# CSI2-TX2-XAVIER_Rev02.net
KiCad netlist of a schematic drawn in Altium Designer
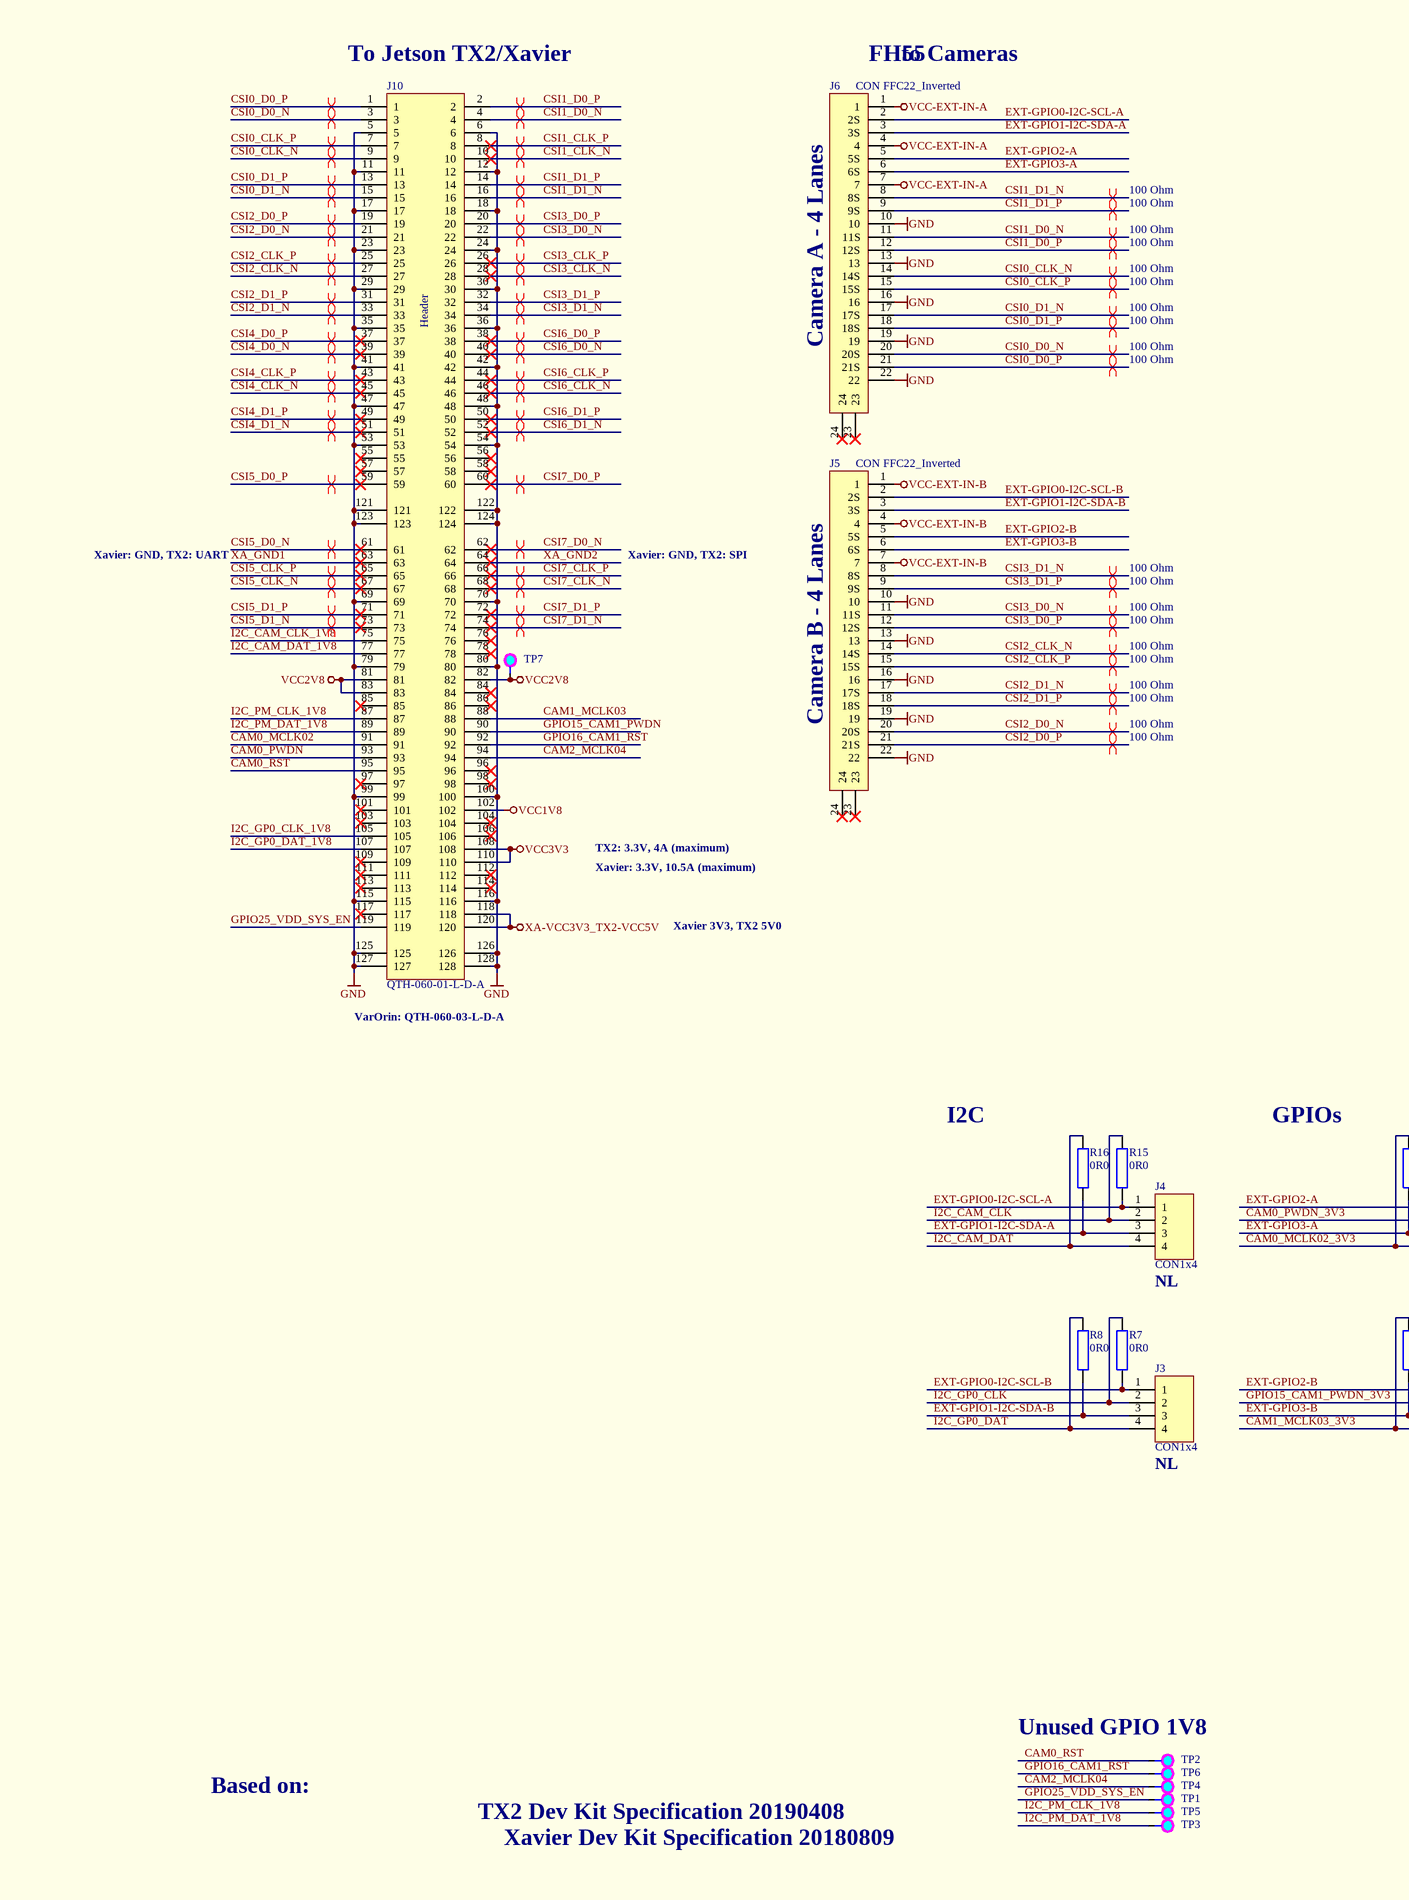
[diagram p0: CSI2-TX2-XAVIER_Rev02.SchDoc, left]
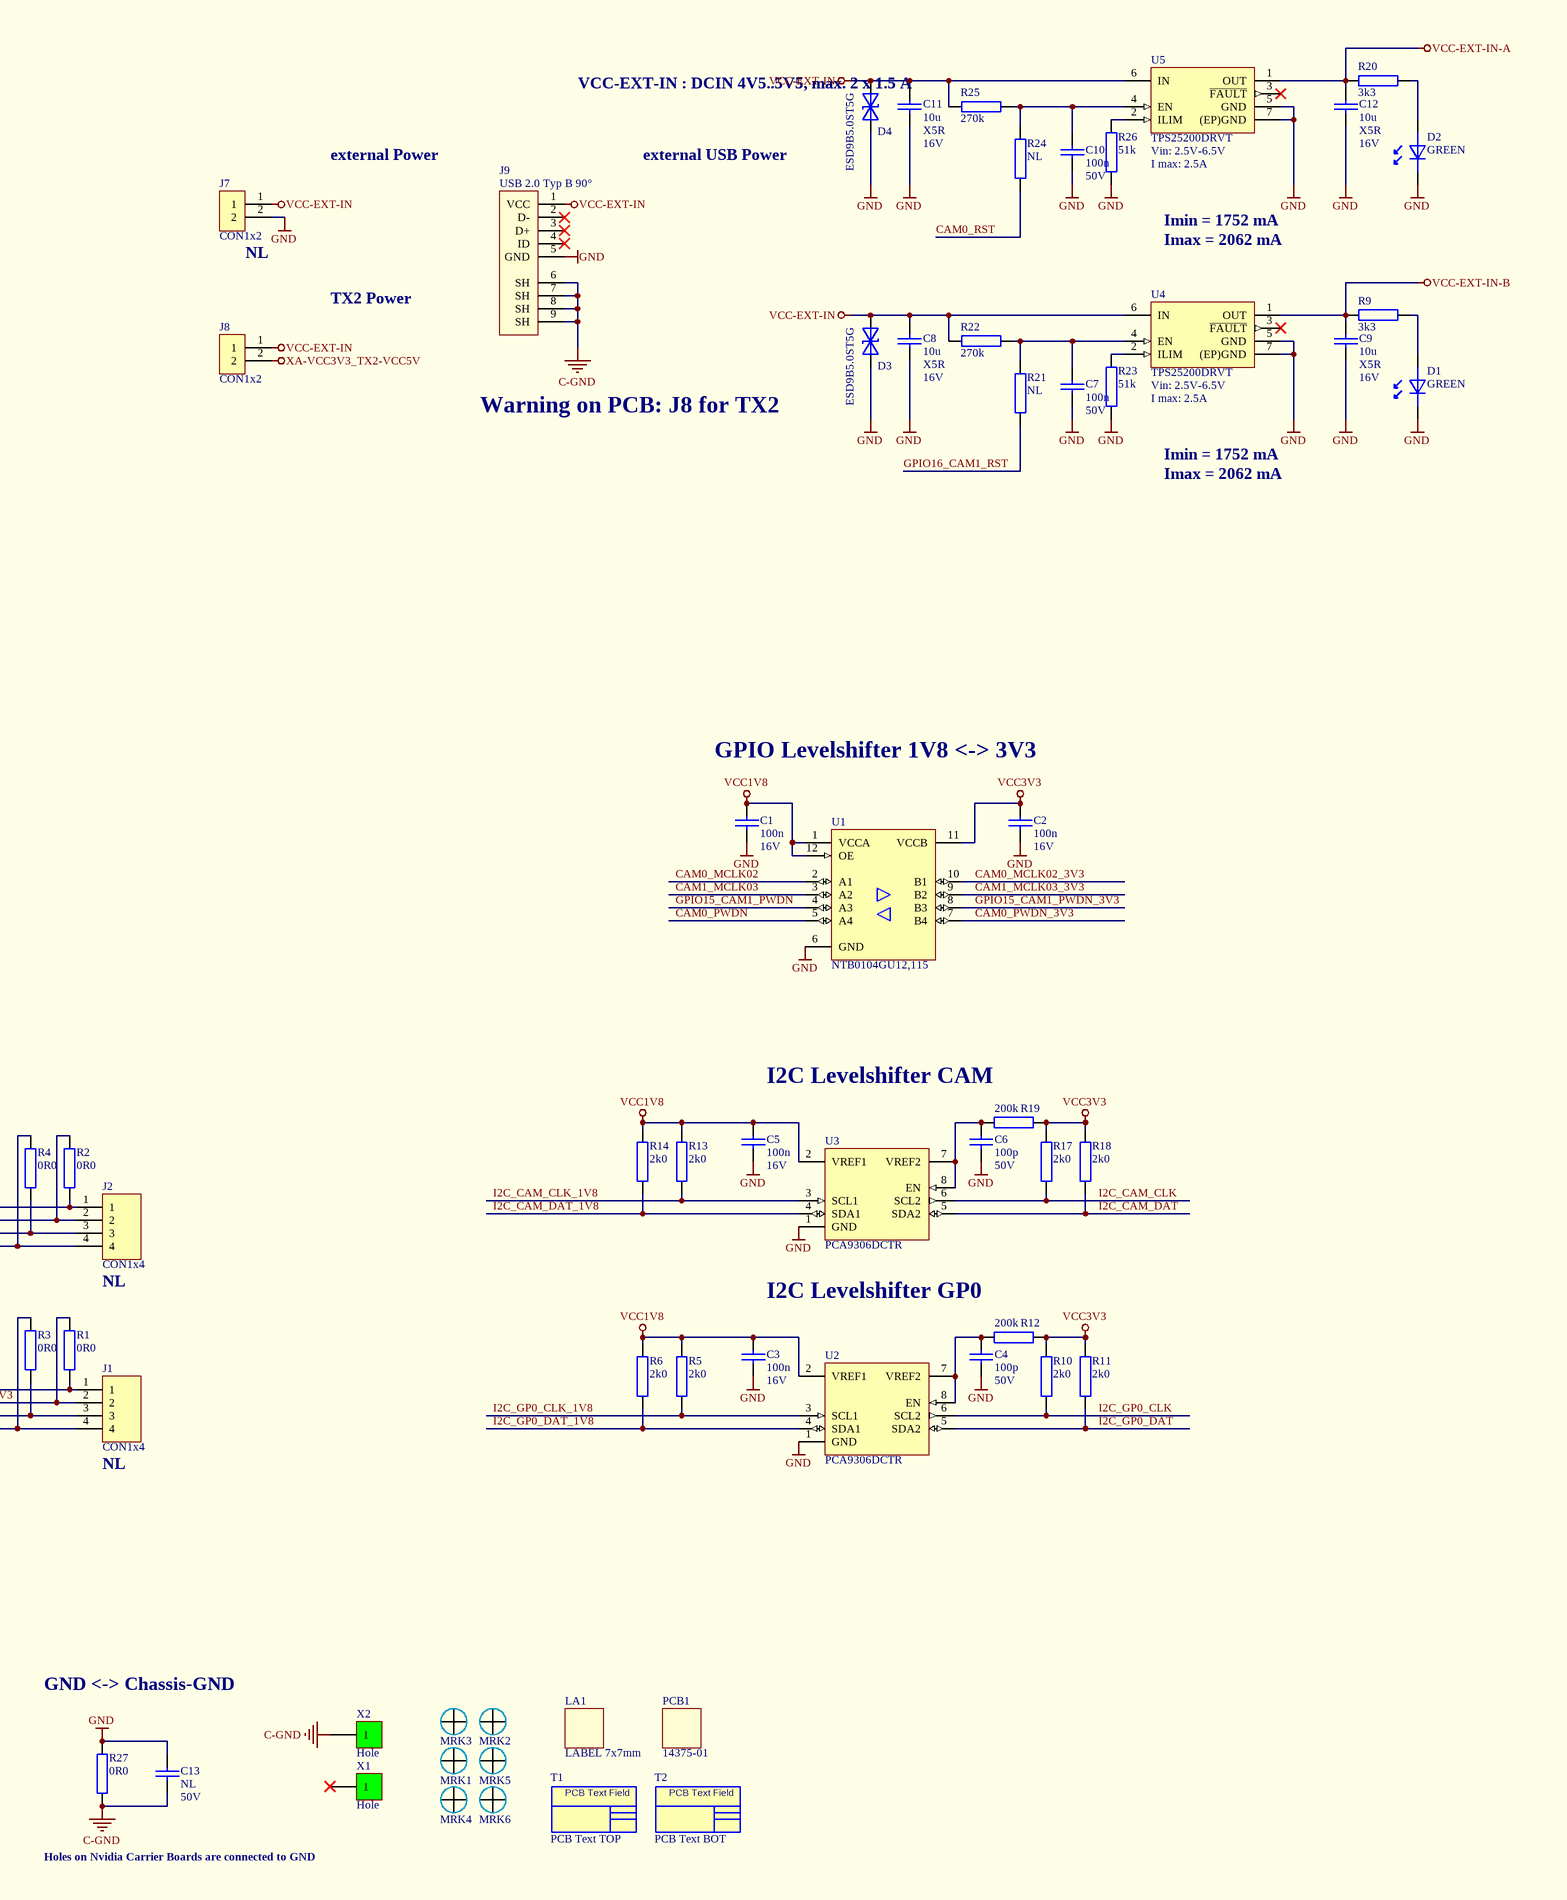
[diagram p1: CSI2-TX2-XAVIER_Rev02.SchDoc, right]

(export (version "E")
  (design (tool "Eeschema 10.0.6"))
  (components
    (comp (ref "C1")
      (value "100n")
      (footprint "C-0402_0.55")
      (description "Capacitor Ceramic SMD/0402/16V/X7R/10%")
      (fields
        (field (name "KHK PART NUMBER") "K8340114")
        (field (name "MANUFACTURER") "several")
        (field (name "VOLTAGE") "16V")
      )
      (libsource (lib "AVT_KHK_Lib") (part "C 100N 10% 16V X7R 402"))
    )
    (comp (ref "C2")
      (value "100n")
      (footprint "C-0402_0.55")
      (description "Capacitor Ceramic SMD/0402/16V/X7R/10%")
      (fields
        (field (name "KHK PART NUMBER") "K8340114")
        (field (name "MANUFACTURER") "several")
        (field (name "VOLTAGE") "16V")
      )
      (libsource (lib "AVT_KHK_Lib") (part "C 100N 10% 16V X7R 402"))
    )
    (comp (ref "C3")
      (value "100n")
      (footprint "C-0402_0.55")
      (description "Capacitor Ceramic SMD/0402/16V/X7R/10%")
      (fields
        (field (name "KHK PART NUMBER") "K8340114")
        (field (name "MANUFACTURER") "several")
        (field (name "VOLTAGE") "16V")
      )
      (libsource (lib "AVT_KHK_Lib") (part "C 100N 10% 16V X7R 402"))
    )
    (comp (ref "C4")
      (value "100p")
      (footprint "C-0402_0.55")
      (description "Capacitor Ceramic SMD/0402/50V/X7R/10%")
      (fields
        (field (name "KHK PART NUMBER") "K8340145")
        (field (name "MANUFACTURER") "several")
        (field (name "VOLTAGE") "50V")
      )
      (libsource (lib "AVT_KHK_Lib") (part "C 100P 50V X7R 0402"))
    )
    (comp (ref "C5")
      (value "100n")
      (footprint "C-0402_0.55")
      (description "Capacitor Ceramic SMD/0402/16V/X7R/10%")
      (fields
        (field (name "KHK PART NUMBER") "K8340114")
        (field (name "MANUFACTURER") "several")
        (field (name "VOLTAGE") "16V")
      )
      (libsource (lib "AVT_KHK_Lib") (part "C 100N 10% 16V X7R 402"))
    )
    (comp (ref "C6")
      (value "100p")
      (footprint "C-0402_0.55")
      (description "Capacitor Ceramic SMD/0402/50V/X7R/10%")
      (fields
        (field (name "KHK PART NUMBER") "K8340145")
        (field (name "MANUFACTURER") "several")
        (field (name "VOLTAGE") "50V")
      )
      (libsource (lib "AVT_KHK_Lib") (part "C 100P 50V X7R 0402"))
    )
    (comp (ref "C7")
      (value "100n")
      (footprint "C-0603_1.0")
      (description "Capacitor Ceramic SMD/0603/50V/X7R/10%")
      (fields
        (field (name "KHK PART NUMBER") "K8340023")
        (field (name "MANUFACTURER") "several")
        (field (name "VOLTAGE") "50V")
      )
      (libsource (lib "AVT_KHK_Lib") (part "C 100N 50V X7R 0603"))
    )
    (comp (ref "C8")
      (value "10u")
      (footprint "C-0805_1.4")
      (description "Capacitor Ceramic SMD/0805/16V/X5R/10%")
      (fields
        (field (name "KHK PART NUMBER") "K8340151")
        (field (name "MANUFACTURER") "several")
        (field (name "DIELECTRIC") "X5R")
        (field (name "VOLTAGE") "16V")
      )
      (libsource (lib "AVT_KHK_Lib") (part "C 10U 16V X5R 0805"))
    )
    (comp (ref "C9")
      (value "10u")
      (footprint "C-0805_1.4")
      (description "Capacitor Ceramic SMD/0805/16V/X5R/10%")
      (fields
        (field (name "KHK PART NUMBER") "K8340151")
        (field (name "MANUFACTURER") "several")
        (field (name "DIELECTRIC") "X5R")
        (field (name "VOLTAGE") "16V")
      )
      (libsource (lib "AVT_KHK_Lib") (part "C 10U 16V X5R 0805"))
    )
    (comp (ref "C10")
      (value "100n")
      (footprint "C-0603_1.0")
      (description "Capacitor Ceramic SMD/0603/50V/X7R/10%")
      (fields
        (field (name "KHK PART NUMBER") "K8340023")
        (field (name "MANUFACTURER") "several")
        (field (name "VOLTAGE") "50V")
      )
      (libsource (lib "AVT_KHK_Lib") (part "C 100N 50V X7R 0603"))
    )
    (comp (ref "C11")
      (value "10u")
      (footprint "C-0805_1.4")
      (description "Capacitor Ceramic SMD/0805/16V/X5R/10%")
      (fields
        (field (name "KHK PART NUMBER") "K8340151")
        (field (name "MANUFACTURER") "several")
        (field (name "DIELECTRIC") "X5R")
        (field (name "VOLTAGE") "16V")
      )
      (libsource (lib "AVT_KHK_Lib") (part "C 10U 16V X5R 0805"))
    )
    (comp (ref "C12")
      (value "10u")
      (footprint "C-0805_1.4")
      (description "Capacitor Ceramic SMD/0805/16V/X5R/10%")
      (fields
        (field (name "KHK PART NUMBER") "K8340151")
        (field (name "MANUFACTURER") "several")
        (field (name "DIELECTRIC") "X5R")
        (field (name "VOLTAGE") "16V")
      )
      (libsource (lib "AVT_KHK_Lib") (part "C 10U 16V X5R 0805"))
    )
    (comp (ref "C13")
      (value "NL")
      (footprint "C-0603_1.0")
      (description "Capacitor Ceramic SMD/0603/50V/X7R/10%")
      (fields
        (field (name "MANUFACTURER") "several")
        (field (name "TOLERANCE") "10%")
        (field (name "VOLTAGE") "50V")
      )
      (libsource (lib "AVT_KHK_Lib") (part "C X 0603"))
    )
    (comp (ref "D1")
      (value "GREEN")
      (footprint "D-0603-LED")
      (description "Chip LED green 430mcd")
      (fields (field (name "KHK PART NUMBER") "8172") (field (name "MANUFACTURER") "Würth"))
      (libsource (lib "AVT_KHK_Lib") (part "D LED 0603 green"))
    )
    (comp (ref "D2")
      (value "GREEN")
      (footprint "D-0603-LED")
      (description "Chip LED green 430mcd")
      (fields (field (name "KHK PART NUMBER") "8172") (field (name "MANUFACTURER") "Würth"))
      (libsource (lib "AVT_KHK_Lib") (part "D LED 0603 green"))
    )
    (comp (ref "D3")
      (value "ESD9B5.0ST5G")
      (footprint "D-SOD923")
      (description "DIODE TVS; 400W; 5.8-7.8V; BIDIRECT")
      (fields (field (name "KHK PART NUMBER") "7250") (field (name "MANUFACTURER") "ON Semiconductor"))
      (libsource (lib "AVT_KHK_Lib") (part "D ESD9B5.0ST5G"))
    )
    (comp (ref "D4")
      (value "ESD9B5.0ST5G")
      (footprint "D-SOD923")
      (description "DIODE TVS; 400W; 5.8-7.8V; BIDIRECT")
      (fields (field (name "KHK PART NUMBER") "7250") (field (name "MANUFACTURER") "ON Semiconductor"))
      (libsource (lib "AVT_KHK_Lib") (part "D ESD9B5.0ST5G"))
    )
    (comp (ref "J1")
      (value "CON1x4")
      (footprint "CON 1x4 RM2.54")
      (description "Stiftleiste; 1x4; 2.54mm; gerade")
      (fields (field (name "MANUFACTURER") "Harwin") (field (name "MANUFACTURER PART NUMBER") "M20-999 0445"))
      (libsource (lib "AVT_KHK_Lib") (part "CON 1x4 2.54"))
    )
    (comp (ref "J2")
      (value "CON1x4")
      (footprint "CON 1x4 RM2.54")
      (description "Stiftleiste; 1x4; 2.54mm; gerade")
      (fields (field (name "MANUFACTURER") "Harwin") (field (name "MANUFACTURER PART NUMBER") "M20-999 0445"))
      (libsource (lib "AVT_KHK_Lib") (part "CON 1x4 2.54"))
    )
    (comp (ref "J3")
      (value "CON1x4")
      (footprint "CON 1x4 RM2.54")
      (description "Stiftleiste; 1x4; 2.54mm; gerade")
      (fields (field (name "MANUFACTURER") "Harwin") (field (name "MANUFACTURER PART NUMBER") "M20-999 0445"))
      (libsource (lib "AVT_KHK_Lib") (part "CON 1x4 2.54"))
    )
    (comp (ref "J4")
      (value "CON1x4")
      (footprint "CON 1x4 RM2.54")
      (description "Stiftleiste; 1x4; 2.54mm; gerade")
      (fields (field (name "MANUFACTURER") "Harwin") (field (name "MANUFACTURER PART NUMBER") "M20-999 0445"))
      (libsource (lib "AVT_KHK_Lib") (part "CON 1x4 2.54"))
    )
    (comp (ref "J5")
      (value "CON FFC22_Inverted")
      (footprint "J-FH55-22S-0.5SH - Inverted Pins")
      (description "FFC Connector 0.5mm shielded")
      (fields
        (field (name "KHK PART NUMBER") "10357")
        (field (name "MANUFACTURER PART NUMBER") "FH55-22S-0.5SH")
      )
      (libsource (lib "AVT_KHK_Lib") (part "CON FFC22_FH55-22S-0.5SH_Inverted"))
    )
    (comp (ref "J6")
      (value "CON FFC22_Inverted")
      (footprint "J-FH55-22S-0.5SH - Inverted Pins")
      (description "FFC Connector 0.5mm shielded")
      (fields
        (field (name "KHK PART NUMBER") "10357")
        (field (name "MANUFACTURER PART NUMBER") "FH55-22S-0.5SH")
      )
      (libsource (lib "AVT_KHK_Lib") (part "CON FFC22_FH55-22S-0.5SH_Inverted"))
    )
    (comp (ref "J7")
      (value "CON1x2")
      (footprint "CON 1x2 RM2.54")
      (description "Stiftleiste; 1x2; 2.54mm; gerade")
      (fields
        (field (name "MANUFACTURER") "fischer elektronik")
        (field (name "MANUFACTURER PART NUMBER") "SL 11 124 2 G")
      )
      (libsource (lib "AVT_KHK_Lib") (part "CON 1x2 2.54"))
    )
    (comp (ref "J8")
      (value "CON1x2")
      (footprint "CON 1x2 RM2.54")
      (description "Stiftleiste; 1x2; 2.54mm; gerade")
      (fields
        (field (name "MANUFACTURER") "fischer elektronik")
        (field (name "MANUFACTURER PART NUMBER") "SL 11 124 2 G")
      )
      (libsource (lib "AVT_KHK_Lib") (part "CON 1x2 2.54"))
    )
    (comp (ref "J9")
      (value "USB 2.0 Typ B 90°")
      (footprint "J-629105150521")
      (description "Micro USB 2.0 Typ B 90°")
      (fields (field (name "KHK PART NUMBER") "14360") (field (name "MANUFACTURER") "WE"))
      (libsource (lib "Connector") (part "CON USB 2.0 Typ B 90°"))
    )
    (comp (ref "J10")
      (value "QTH-060-01-L-D-A")
      (footprint "J-QTH-060-XX-X-D-A")
      (description "120pin B2B Header 0.5 pitch 10.27mm Height")
      (fields (field (name "MANUFACTURER") "SamTec") (field (name "KHK PART NUMBER") "10657"))
      (libsource (lib "AVT_KHK_Lib") (part "CON QTH-060-01-L-D-A"))
    )
    (comp (ref "LA1")
      (value "LABEL 7x7mm")
      (footprint "PCB LABEL 7x7")
      (fields (field (name "MANUFACTURER") "several"))
      (libsource (lib "AVT_KHK_Lib") (part "PCB LABEL 7x7"))
    )
    (comp (ref "MRK1")
      (value "Marker Single Layer")
      (footprint "PCB_Marker_Pad_top")
      (description "Position Marker for PCBs")
      (libsource (lib "AVT_KHK_Lib") (part "PCB Marker Pad Single Layer"))
    )
    (comp (ref "MRK2")
      (value "Marker Single Layer")
      (footprint "PCB_Marker_Pad_top")
      (description "Position Marker for PCBs")
      (libsource (lib "AVT_KHK_Lib") (part "PCB Marker Pad Single Layer"))
    )
    (comp (ref "MRK3")
      (value "Marker Single Layer")
      (footprint "PCB_Marker_Pad_top")
      (description "Position Marker for PCBs")
      (libsource (lib "AVT_KHK_Lib") (part "PCB Marker Pad Single Layer"))
    )
    (comp (ref "MRK4")
      (value "Marker Single Layer")
      (footprint "PCB_Marker_Pad_top")
      (description "Position Marker for PCBs")
      (libsource (lib "AVT_KHK_Lib") (part "PCB Marker Pad Single Layer"))
    )
    (comp (ref "MRK5")
      (value "Marker Single Layer")
      (footprint "PCB_Marker_Pad_top")
      (description "Position Marker for PCBs")
      (libsource (lib "AVT_KHK_Lib") (part "PCB Marker Pad Single Layer"))
    )
    (comp (ref "MRK6")
      (value "Marker Single Layer")
      (footprint "PCB_Marker_Pad_top")
      (description "Position Marker for PCBs")
      (libsource (lib "AVT_KHK_Lib") (part "PCB Marker Pad Single Layer"))
    )
    (comp (ref "PCB1")
      (value "14375-01")
      (description "PCB ML04")
      (fields (field (name "MANUFACTURER") "several"))
      (libsource (lib "AVT_KHK_Lib") (part "PCB"))
    )
    (comp (ref "R1")
      (value "0R0")
      (footprint "R-0603_0.6")
      (description "Standard Resistor SMD/0603/1%/100mW/TK200")
      (fields (field (name "KHK PART NUMBER") "K8250041") (field (name "MANUFACTURER") "several"))
      (libsource (lib "AVT_KHK_Lib") (part "R 0R0 1% 0603"))
    )
    (comp (ref "R2")
      (value "0R0")
      (footprint "R-0603_0.6")
      (description "Standard Resistor SMD/0603/1%/100mW/TK200")
      (fields (field (name "KHK PART NUMBER") "K8250041") (field (name "MANUFACTURER") "several"))
      (libsource (lib "AVT_KHK_Lib") (part "R 0R0 1% 0603"))
    )
    (comp (ref "R3")
      (value "0R0")
      (footprint "R-0603_0.6")
      (description "Standard Resistor SMD/0603/1%/100mW/TK200")
      (fields (field (name "KHK PART NUMBER") "K8250041") (field (name "MANUFACTURER") "several"))
      (libsource (lib "AVT_KHK_Lib") (part "R 0R0 1% 0603"))
    )
    (comp (ref "R4")
      (value "0R0")
      (footprint "R-0603_0.6")
      (description "Standard Resistor SMD/0603/1%/100mW/TK200")
      (fields (field (name "KHK PART NUMBER") "K8250041") (field (name "MANUFACTURER") "several"))
      (libsource (lib "AVT_KHK_Lib") (part "R 0R0 1% 0603"))
    )
    (comp (ref "R5")
      (value "2k0")
      (footprint "R-0402_0.4")
      (description "Standard Resistor SMD/0402/1%/63mW/TK100")
      (fields (field (name "KHK PART NUMBER") "K8250311") (field (name "MANUFACTURER") "several"))
      (libsource (lib "AVT_KHK_Lib") (part "R 2k0 1% 0402"))
    )
    (comp (ref "R6")
      (value "2k0")
      (footprint "R-0402_0.4")
      (description "Standard Resistor SMD/0402/1%/63mW/TK100")
      (fields (field (name "KHK PART NUMBER") "K8250311") (field (name "MANUFACTURER") "several"))
      (libsource (lib "AVT_KHK_Lib") (part "R 2k0 1% 0402"))
    )
    (comp (ref "R7")
      (value "0R0")
      (footprint "R-0603_0.6")
      (description "Standard Resistor SMD/0603/1%/100mW/TK100")
      (fields (field (name "KHK PART NUMBER") "K8250041") (field (name "MANUFACTURER") "several"))
      (libsource (lib "AVT_KHK_Lib") (part "R 0R0 1% 0603"))
    )
    (comp (ref "R8")
      (value "0R0")
      (footprint "R-0603_0.6")
      (description "Standard Resistor SMD/0603/1%/100mW/TK100")
      (fields (field (name "KHK PART NUMBER") "K8250041") (field (name "MANUFACTURER") "several"))
      (libsource (lib "AVT_KHK_Lib") (part "R 0R0 1% 0603"))
    )
    (comp (ref "R9")
      (value "3k3")
      (footprint "R-0603_0.6")
      (description "Standard Resistor SMD/0603/1%/100mW/TK100")
      (fields (field (name "KHK PART NUMBER") "K8250070") (field (name "MANUFACTURER") "several"))
      (libsource (lib "AVT_KHK_Lib") (part "R 3K3 1% 0603"))
    )
    (comp (ref "R10")
      (value "2k0")
      (footprint "R-0402_0.4")
      (description "Standard Resistor SMD/0402/1%/63mW/TK100")
      (fields (field (name "KHK PART NUMBER") "K8250311") (field (name "MANUFACTURER") "several"))
      (libsource (lib "AVT_KHK_Lib") (part "R 2k0 1% 0402"))
    )
    (comp (ref "R11")
      (value "2k0")
      (footprint "R-0402_0.4")
      (description "Standard Resistor SMD/0402/1%/63mW/TK100")
      (fields (field (name "KHK PART NUMBER") "K8250311") (field (name "MANUFACTURER") "several"))
      (libsource (lib "AVT_KHK_Lib") (part "R 2k0 1% 0402"))
    )
    (comp (ref "R12")
      (value "200k")
      (footprint "R-0402_0.4")
      (description "Standard Resistor SMD/0402/1%/63mW/TK100")
      (fields (field (name "KHK PART NUMBER") "K8250280") (field (name "MANUFACTURER") "several"))
      (libsource (lib "AVT_KHK_Lib") (part "R 200K 1% 0402"))
    )
    (comp (ref "R13")
      (value "2k0")
      (footprint "R-0402_0.4")
      (description "Standard Resistor SMD/0402/1%/63mW/TK100")
      (fields (field (name "KHK PART NUMBER") "K8250311") (field (name "MANUFACTURER") "several"))
      (libsource (lib "AVT_KHK_Lib") (part "R 2k0 1% 0402"))
    )
    (comp (ref "R14")
      (value "2k0")
      (footprint "R-0402_0.4")
      (description "Standard Resistor SMD/0402/1%/63mW/TK100")
      (fields (field (name "KHK PART NUMBER") "K8250311") (field (name "MANUFACTURER") "several"))
      (libsource (lib "AVT_KHK_Lib") (part "R 2k0 1% 0402"))
    )
    (comp (ref "R15")
      (value "0R0")
      (footprint "R-0603_0.6")
      (description "Standard Resistor SMD/0603/1%/100mW/TK100")
      (fields (field (name "KHK PART NUMBER") "K8250041") (field (name "MANUFACTURER") "several"))
      (libsource (lib "AVT_KHK_Lib") (part "R 0R0 1% 0603"))
    )
    (comp (ref "R16")
      (value "0R0")
      (footprint "R-0603_0.6")
      (description "Standard Resistor SMD/0603/1%/100mW/TK100")
      (fields (field (name "KHK PART NUMBER") "K8250041") (field (name "MANUFACTURER") "several"))
      (libsource (lib "AVT_KHK_Lib") (part "R 0R0 1% 0603"))
    )
    (comp (ref "R17")
      (value "2k0")
      (footprint "R-0402_0.4")
      (description "Standard Resistor SMD/0402/1%/63mW/TK100")
      (fields (field (name "KHK PART NUMBER") "K8250311") (field (name "MANUFACTURER") "several"))
      (libsource (lib "AVT_KHK_Lib") (part "R 2k0 1% 0402"))
    )
    (comp (ref "R18")
      (value "2k0")
      (footprint "R-0402_0.4")
      (description "Standard Resistor SMD/0402/1%/63mW/TK100")
      (fields (field (name "KHK PART NUMBER") "K8250311") (field (name "MANUFACTURER") "several"))
      (libsource (lib "AVT_KHK_Lib") (part "R 2k0 1% 0402"))
    )
    (comp (ref "R19")
      (value "200k")
      (footprint "R-0402_0.4")
      (description "Standard Resistor SMD/0402/1%/63mW/TK100")
      (fields (field (name "KHK PART NUMBER") "K8250280") (field (name "MANUFACTURER") "several"))
      (libsource (lib "AVT_KHK_Lib") (part "R 200K 1% 0402"))
    )
    (comp (ref "R20")
      (value "3k3")
      (footprint "R-0603_0.6")
      (description "Standard Resistor SMD/0603/1%/100mW/TK100")
      (fields (field (name "KHK PART NUMBER") "K8250070") (field (name "MANUFACTURER") "several"))
      (libsource (lib "AVT_KHK_Lib") (part "R 3K3 1% 0603"))
    )
    (comp (ref "R21")
      (value "NL")
      (footprint "R-0603_0.6")
      (description "Standard Resistor SMD/0603/1%/100mW/TK200")
      (fields (field (name "TOLERANCE") "1%"))
      (libsource (lib "AVT_KHK_Lib") (part "R X 0603"))
    )
    (comp (ref "R22")
      (value "270k")
      (footprint "R-0603_0.6")
      (description "Standard Resistor SMD/0603/1%/100mW/TK100")
      (fields (field (name "KHK PART NUMBER") "K8250170") (field (name "MANUFACTURER") "several"))
      (libsource (lib "AVT_KHK_Lib") (part "R 270K 1% 0603"))
    )
    (comp (ref "R23")
      (value "51k")
      (footprint "R-0603_0.6")
      (description "Standard Resistor SMD/0603/1%/100mW/TK100")
      (fields (field (name "KHK PART NUMBER") "K8250156") (field (name "MANUFACTURER") "several"))
      (libsource (lib "AVT_KHK_Lib") (part "R 51K 1% 0603"))
    )
    (comp (ref "R24")
      (value "NL")
      (footprint "R-0603_0.6")
      (description "Standard Resistor SMD/0603/1%/100mW/TK200")
      (fields (field (name "TOLERANCE") "1%"))
      (libsource (lib "AVT_KHK_Lib") (part "R X 0603"))
    )
    (comp (ref "R25")
      (value "270k")
      (footprint "R-0603_0.6")
      (description "Standard Resistor SMD/0603/1%/100mW/TK100")
      (fields (field (name "KHK PART NUMBER") "K8250170") (field (name "MANUFACTURER") "several"))
      (libsource (lib "AVT_KHK_Lib") (part "R 270K 1% 0603"))
    )
    (comp (ref "R26")
      (value "51k")
      (footprint "R-0603_0.6")
      (description "Standard Resistor SMD/0603/1%/100mW/TK100")
      (fields (field (name "KHK PART NUMBER") "K8250156") (field (name "MANUFACTURER") "several"))
      (libsource (lib "AVT_KHK_Lib") (part "R 51K 1% 0603"))
    )
    (comp (ref "R27")
      (value "0R0")
      (footprint "R-0603_0.6")
      (description "Standard Resistor SMD/0603/1%/100mW/TK200")
      (fields (field (name "KHK PART NUMBER") "K8250041") (field (name "MANUFACTURER") "several"))
      (libsource (lib "AVT_KHK_Lib") (part "R 0R0 1% 0603"))
    )
    (comp (ref "T1")
      (value "PCB Text TOP")
      (footprint "PCB TEXTFIELD TOP 2")
      (description "PCB Textfield TOP")
      (libsource (lib "AVT_KHK_Lib") (part "PCB TEXT FIELD TOP"))
    )
    (comp (ref "T2")
      (value "PCB Text BOT")
      (footprint "PCB TEXTFIELD BOT 2")
      (description "PCB Textfield BOT")
      (libsource (lib "AVT_KHK_Lib") (part "PCB TEXT FIELD BOT"))
    )
    (comp (ref "TP1")
      (value "TP")
      (footprint "TP_16_10")
      (description "Testpoint: Pad=1,6mm; Hole=1,0mm")
      (libsource (lib "AVT_KHK_Lib") (part "TP_16_10"))
    )
    (comp (ref "TP2")
      (value "TP")
      (footprint "TP_16_10")
      (description "Testpoint: Pad=1,6mm; Hole=1,0mm")
      (libsource (lib "AVT_KHK_Lib") (part "TP_16_10"))
    )
    (comp (ref "TP3")
      (value "TP")
      (footprint "TP_16_10")
      (description "Testpoint: Pad=1,6mm; Hole=1,0mm")
      (libsource (lib "AVT_KHK_Lib") (part "TP_16_10"))
    )
    (comp (ref "TP4")
      (value "TP")
      (footprint "TP_16_10")
      (description "Testpoint: Pad=1,6mm; Hole=1,0mm")
      (libsource (lib "AVT_KHK_Lib") (part "TP_16_10"))
    )
    (comp (ref "TP5")
      (value "TP")
      (footprint "TP_16_10")
      (description "Testpoint: Pad=1,6mm; Hole=1,0mm")
      (libsource (lib "AVT_KHK_Lib") (part "TP_16_10"))
    )
    (comp (ref "TP6")
      (value "TP")
      (footprint "TP_16_10")
      (description "Testpoint: Pad=1,6mm; Hole=1,0mm")
      (libsource (lib "AVT_KHK_Lib") (part "TP_16_10"))
    )
    (comp (ref "TP7")
      (value "TP")
      (footprint "TP_16_10")
      (description "Testpoint: Pad=1,6mm; Hole=1,0mm")
      (libsource (lib "AVT_KHK_Lib") (part "TP_16_10"))
    )
    (comp (ref "U1")
      (value "NTB0104GU12,115")
      (footprint "IC-XQFN12_1.7x2x0.5")
      (description "IC/LOGIC/Levelshifter;Auto-Dir;Bidirectional;Push-Pull;-40-+125°C/")
      (fields (field (name "MANUFACTURER") "NXP") (field (name "KHK PART NUMBER") "14383"))
      (libsource (lib "AVT_KHK_Lib") (part "IC NTB0104GU12,115"))
    )
    (comp (ref "U2")
      (value "PCA9306DCTR")
      (footprint "IC-TSSOP8_3.15x4.25x1.3")
      (description "IC/LOGIC/LEVELSHIFTER;I2C;AUTO-DIR;1V2-5V/SSOP-8/4.25x3.15x1.3mm")
      (fields (field (name "KHK PART NUMBER") "9555") (field (name "MANUFACTURER") "TI"))
      (libsource (lib "AVT_KHK_Lib") (part "IC PCA9306DCTR"))
    )
    (comp (ref "U3")
      (value "PCA9306DCTR")
      (footprint "IC-TSSOP8_3.15x4.25x1.3")
      (description "IC/LOGIC/LEVELSHIFTER;I2C;AUTO-DIR;1V2-5V/SSOP-8/4.25x3.15x1.3mm")
      (fields (field (name "KHK PART NUMBER") "9555") (field (name "MANUFACTURER") "TI"))
      (libsource (lib "AVT_KHK_Lib") (part "IC PCA9306DCTR"))
    )
    (comp (ref "U4")
      (value "TPS25200DRVT")
      (footprint "IC-DFN06_2.0x2.0x0.8")
      (description "IC/PWR/LOADSW;2V5-6V5;2A5;0R099/6-WDFN/2x2x0.8mm")
      (fields
        (field (name "KHK PART NUMBER") "14277")
        (field (name "MANUFACTURER") "Texas Instruments")
        (field (name "VIN") "2.5V-6.5V")
        (field (name "I MAX") "2.5A")
      )
      (libsource (lib "AVT_KHK_Lib") (part "IC  TPS25200DRVT"))
    )
    (comp (ref "U5")
      (value "TPS25200DRVT")
      (footprint "IC-DFN06_2.0x2.0x0.8")
      (description "IC/PWR/LOADSW;2V5-6V5;2A5;0R099/6-WDFN/2x2x0.8mm")
      (fields
        (field (name "KHK PART NUMBER") "14277")
        (field (name "MANUFACTURER") "Texas Instruments")
        (field (name "VIN") "2.5V-6.5V")
        (field (name "I MAX") "2.5A")
      )
      (libsource (lib "AVT_KHK_Lib") (part "IC  TPS25200DRVT"))
    )
    (comp (ref "X1")
      (value "Hole")
      (footprint "HOLE-3.2-6.0-DK")
      (description "HOLE M3")
      (libsource (lib "AVT_KHK_Lib") (part "PCB HOLE M3-6-DK"))
    )
    (comp (ref "X2")
      (value "Hole")
      (footprint "HOLE-3.2-6.0-DK")
      (description "HOLE M3")
      (libsource (lib "AVT_KHK_Lib") (part "PCB HOLE M3-6-DK"))
    )
  )
  (nets
    (net (code "1") (name "/CAM0_MCLK02") (class "Default")
      (node (ref "J10") (pin "91") (pinfunction "91_91") (pintype "passive"))
      (node (ref "U1") (pin "2") (pinfunction "A1_2") (pintype "bidirectional"))
    )
    (net (code "2") (name "/CAM0_MCLK02_3V3") (class "Default")
      (node (ref "J2") (pin "4") (pinfunction "4_4") (pintype "passive"))
      (node (ref "R4") (pin "2") (pinfunction "2_2") (pintype "passive"))
      (node (ref "U1") (pin "10") (pinfunction "B1_10") (pintype "bidirectional"))
    )
    (net (code "3") (name "/CAM0_PWDN") (class "Default")
      (node (ref "J10") (pin "93") (pinfunction "93_93") (pintype "passive"))
      (node (ref "U1") (pin "5") (pinfunction "A4_5") (pintype "bidirectional"))
    )
    (net (code "4") (name "/CAM0_PWDN_3V3") (class "Default")
      (node (ref "J2") (pin "2") (pinfunction "2_2") (pintype "passive"))
      (node (ref "R2") (pin "2") (pinfunction "2_2") (pintype "passive"))
      (node (ref "U1") (pin "7") (pinfunction "B4_7") (pintype "bidirectional"))
    )
    (net (code "5") (name "/CAM0_RST") (class "Default")
      (node (ref "J10") (pin "95") (pinfunction "95_95") (pintype "passive"))
      (node (ref "R24") (pin "1") (pinfunction "1_1") (pintype "passive"))
      (node (ref "TP2") (pin "1") (pinfunction "1_1") (pintype "passive"))
    )
    (net (code "6") (name "/CAM1_MCLK03") (class "Default")
      (node (ref "J10") (pin "88") (pinfunction "88_88") (pintype "passive"))
      (node (ref "U1") (pin "3") (pinfunction "A2_3") (pintype "bidirectional"))
    )
    (net (code "7") (name "/CAM1_MCLK03_3V3") (class "Default")
      (node (ref "J1") (pin "4") (pinfunction "4_4") (pintype "passive"))
      (node (ref "R3") (pin "2") (pinfunction "2_2") (pintype "passive"))
      (node (ref "U1") (pin "9") (pinfunction "B2_9") (pintype "bidirectional"))
    )
    (net (code "8") (name "/CAM2_MCLK04") (class "Default")
      (node (ref "J10") (pin "94") (pinfunction "94_94") (pintype "passive"))
      (node (ref "TP4") (pin "1") (pinfunction "1_1") (pintype "passive"))
    )
    (net (code "9") (name "/CSI0_CLK_N") (class "Default")
      (node (ref "J10") (pin "9") (pinfunction "9_9") (pintype "passive"))
      (node (ref "J6") (pin "14") (pinfunction "14S_14") (pintype "passive"))
    )
    (net (code "10") (name "/CSI0_CLK_P") (class "Default")
      (node (ref "J10") (pin "7") (pinfunction "7_7") (pintype "passive"))
      (node (ref "J6") (pin "15") (pinfunction "15S_15") (pintype "passive"))
    )
    (net (code "11") (name "/CSI0_D0_N") (class "Default")
      (node (ref "J10") (pin "3") (pinfunction "3_3") (pintype "passive"))
      (node (ref "J6") (pin "20") (pinfunction "20S_20") (pintype "passive"))
    )
    (net (code "12") (name "/CSI0_D0_P") (class "Default")
      (node (ref "J10") (pin "1") (pinfunction "1_1") (pintype "passive"))
      (node (ref "J6") (pin "21") (pinfunction "21S_21") (pintype "passive"))
    )
    (net (code "13") (name "/CSI0_D1_N") (class "Default")
      (node (ref "J10") (pin "15") (pinfunction "15_15") (pintype "passive"))
      (node (ref "J6") (pin "17") (pinfunction "17S_17") (pintype "passive"))
    )
    (net (code "14") (name "/CSI0_D1_P") (class "Default")
      (node (ref "J10") (pin "13") (pinfunction "13_13") (pintype "passive"))
      (node (ref "J6") (pin "18") (pinfunction "18S_18") (pintype "passive"))
    )
    (net (code "15") (name "/CSI1_CLK_N") (class "Default")
      (node (ref "J10") (pin "10") (pinfunction "10_10") (pintype "passive+no_connect"))
    )
    (net (code "16") (name "/CSI1_CLK_P") (class "Default")
      (node (ref "J10") (pin "8") (pinfunction "8_8") (pintype "passive+no_connect"))
    )
    (net (code "17") (name "/CSI1_D0_N") (class "Default")
      (node (ref "J10") (pin "4") (pinfunction "4_4") (pintype "passive"))
      (node (ref "J6") (pin "11") (pinfunction "11S_11") (pintype "passive"))
    )
    (net (code "18") (name "/CSI1_D0_P") (class "Default")
      (node (ref "J10") (pin "2") (pinfunction "2_2") (pintype "passive"))
      (node (ref "J6") (pin "12") (pinfunction "12S_12") (pintype "passive"))
    )
    (net (code "19") (name "/CSI1_D1_N") (class "Default")
      (node (ref "J10") (pin "16") (pinfunction "16_16") (pintype "passive"))
      (node (ref "J6") (pin "8") (pinfunction "8S_8") (pintype "passive"))
    )
    (net (code "20") (name "/CSI1_D1_P") (class "Default")
      (node (ref "J10") (pin "14") (pinfunction "14_14") (pintype "passive"))
      (node (ref "J6") (pin "9") (pinfunction "9S_9") (pintype "passive"))
    )
    (net (code "21") (name "/CSI2_CLK_N") (class "Default")
      (node (ref "J10") (pin "27") (pinfunction "27_27") (pintype "passive"))
      (node (ref "J5") (pin "14") (pinfunction "14S_14") (pintype "passive"))
    )
    (net (code "22") (name "/CSI2_CLK_P") (class "Default")
      (node (ref "J10") (pin "25") (pinfunction "25_25") (pintype "passive"))
      (node (ref "J5") (pin "15") (pinfunction "15S_15") (pintype "passive"))
    )
    (net (code "23") (name "/CSI2_D0_N") (class "Default")
      (node (ref "J10") (pin "21") (pinfunction "21_21") (pintype "passive"))
      (node (ref "J5") (pin "20") (pinfunction "20S_20") (pintype "passive"))
    )
    (net (code "24") (name "/CSI2_D0_P") (class "Default")
      (node (ref "J10") (pin "19") (pinfunction "19_19") (pintype "passive"))
      (node (ref "J5") (pin "21") (pinfunction "21S_21") (pintype "passive"))
    )
    (net (code "25") (name "/CSI2_D1_N") (class "Default")
      (node (ref "J10") (pin "33") (pinfunction "33_33") (pintype "passive"))
      (node (ref "J5") (pin "17") (pinfunction "17S_17") (pintype "passive"))
    )
    (net (code "26") (name "/CSI2_D1_P") (class "Default")
      (node (ref "J10") (pin "31") (pinfunction "31_31") (pintype "passive"))
      (node (ref "J5") (pin "18") (pinfunction "18S_18") (pintype "passive"))
    )
    (net (code "27") (name "/CSI3_CLK_N") (class "Default")
      (node (ref "J10") (pin "28") (pinfunction "28_28") (pintype "passive+no_connect"))
    )
    (net (code "28") (name "/CSI3_CLK_P") (class "Default")
      (node (ref "J10") (pin "26") (pinfunction "26_26") (pintype "passive+no_connect"))
    )
    (net (code "29") (name "/CSI3_D0_N") (class "Default")
      (node (ref "J10") (pin "22") (pinfunction "22_22") (pintype "passive"))
      (node (ref "J5") (pin "11") (pinfunction "11S_11") (pintype "passive"))
    )
    (net (code "30") (name "/CSI3_D0_P") (class "Default")
      (node (ref "J10") (pin "20") (pinfunction "20_20") (pintype "passive"))
      (node (ref "J5") (pin "12") (pinfunction "12S_12") (pintype "passive"))
    )
    (net (code "31") (name "/CSI3_D1_N") (class "Default")
      (node (ref "J10") (pin "34") (pinfunction "34_34") (pintype "passive"))
      (node (ref "J5") (pin "8") (pinfunction "8S_8") (pintype "passive"))
    )
    (net (code "32") (name "/CSI3_D1_P") (class "Default")
      (node (ref "J10") (pin "32") (pinfunction "32_32") (pintype "passive"))
      (node (ref "J5") (pin "9") (pinfunction "9S_9") (pintype "passive"))
    )
    (net (code "33") (name "/CSI4_CLK_N") (class "Default")
      (node (ref "J10") (pin "45") (pinfunction "45_45") (pintype "passive+no_connect"))
    )
    (net (code "34") (name "/CSI4_CLK_P") (class "Default")
      (node (ref "J10") (pin "43") (pinfunction "43_43") (pintype "passive+no_connect"))
    )
    (net (code "35") (name "/CSI4_D0_N") (class "Default")
      (node (ref "J10") (pin "39") (pinfunction "39_39") (pintype "passive+no_connect"))
    )
    (net (code "36") (name "/CSI4_D0_P") (class "Default")
      (node (ref "J10") (pin "37") (pinfunction "37_37") (pintype "passive+no_connect"))
    )
    (net (code "37") (name "/CSI4_D1_N") (class "Default")
      (node (ref "J10") (pin "51") (pinfunction "51_51") (pintype "passive+no_connect"))
    )
    (net (code "38") (name "/CSI4_D1_P") (class "Default")
      (node (ref "J10") (pin "49") (pinfunction "49_49") (pintype "passive+no_connect"))
    )
    (net (code "39") (name "/CSI5_CLK_N") (class "Default")
      (node (ref "J10") (pin "67") (pinfunction "67_67") (pintype "passive+no_connect"))
    )
    (net (code "40") (name "/CSI5_CLK_P") (class "Default")
      (node (ref "J10") (pin "65") (pinfunction "65_65") (pintype "passive+no_connect"))
    )
    (net (code "41") (name "/CSI5_D0_N") (class "Default")
      (node (ref "J10") (pin "61") (pinfunction "61_61") (pintype "passive+no_connect"))
    )
    (net (code "42") (name "/CSI5_D0_P") (class "Default")
      (node (ref "J10") (pin "59") (pinfunction "59_59") (pintype "passive+no_connect"))
    )
    (net (code "43") (name "/CSI5_D1_N") (class "Default")
      (node (ref "J10") (pin "73") (pinfunction "73_73") (pintype "passive+no_connect"))
    )
    (net (code "44") (name "/CSI5_D1_P") (class "Default")
      (node (ref "J10") (pin "71") (pinfunction "71_71") (pintype "passive+no_connect"))
    )
    (net (code "45") (name "/CSI6_CLK_N") (class "Default")
      (node (ref "J10") (pin "46") (pinfunction "46_46") (pintype "passive+no_connect"))
    )
    (net (code "46") (name "/CSI6_CLK_P") (class "Default")
      (node (ref "J10") (pin "44") (pinfunction "44_44") (pintype "passive+no_connect"))
    )
    (net (code "47") (name "/CSI6_D0_N") (class "Default")
      (node (ref "J10") (pin "40") (pinfunction "40_40") (pintype "passive+no_connect"))
    )
    (net (code "48") (name "/CSI6_D0_P") (class "Default")
      (node (ref "J10") (pin "38") (pinfunction "38_38") (pintype "passive+no_connect"))
    )
    (net (code "49") (name "/CSI6_D1_N") (class "Default")
      (node (ref "J10") (pin "52") (pinfunction "52_52") (pintype "passive+no_connect"))
    )
    (net (code "50") (name "/CSI6_D1_P") (class "Default")
      (node (ref "J10") (pin "50") (pinfunction "50_50") (pintype "passive+no_connect"))
    )
    (net (code "51") (name "/CSI7_CLK_N") (class "Default")
      (node (ref "J10") (pin "68") (pinfunction "68_68") (pintype "passive+no_connect"))
    )
    (net (code "52") (name "/CSI7_CLK_P") (class "Default")
      (node (ref "J10") (pin "66") (pinfunction "66_66") (pintype "passive+no_connect"))
    )
    (net (code "53") (name "/CSI7_D0_N") (class "Default")
      (node (ref "J10") (pin "62") (pinfunction "62_62") (pintype "passive+no_connect"))
    )
    (net (code "54") (name "/CSI7_D0_P") (class "Default")
      (node (ref "J10") (pin "60") (pinfunction "60_60") (pintype "passive+no_connect"))
    )
    (net (code "55") (name "/CSI7_D1_N") (class "Default")
      (node (ref "J10") (pin "74") (pinfunction "74_74") (pintype "passive+no_connect"))
    )
    (net (code "56") (name "/CSI7_D1_P") (class "Default")
      (node (ref "J10") (pin "72") (pinfunction "72_72") (pintype "passive+no_connect"))
    )
    (net (code "57") (name "/EXT-GPIO0-I2C-SCL-A") (class "Default")
      (node (ref "J4") (pin "1") (pinfunction "1_1") (pintype "passive"))
      (node (ref "J6") (pin "2") (pinfunction "2S_2") (pintype "passive"))
      (node (ref "R15") (pin "1") (pinfunction "1_1") (pintype "passive"))
    )
    (net (code "58") (name "/EXT-GPIO0-I2C-SCL-B") (class "Default")
      (node (ref "J3") (pin "1") (pinfunction "1_1") (pintype "passive"))
      (node (ref "J5") (pin "2") (pinfunction "2S_2") (pintype "passive"))
      (node (ref "R7") (pin "1") (pinfunction "1_1") (pintype "passive"))
    )
    (net (code "59") (name "/EXT-GPIO1-I2C-SDA-A") (class "Default")
      (node (ref "J4") (pin "3") (pinfunction "3_3") (pintype "passive"))
      (node (ref "J6") (pin "3") (pinfunction "3S_3") (pintype "passive"))
      (node (ref "R16") (pin "1") (pinfunction "1_1") (pintype "passive"))
    )
    (net (code "60") (name "/EXT-GPIO1-I2C-SDA-B") (class "Default")
      (node (ref "J3") (pin "3") (pinfunction "3_3") (pintype "passive"))
      (node (ref "J5") (pin "3") (pinfunction "3S_3") (pintype "passive"))
      (node (ref "R8") (pin "1") (pinfunction "1_1") (pintype "passive"))
    )
    (net (code "61") (name "/EXT-GPIO2-A") (class "Default")
      (node (ref "J2") (pin "1") (pinfunction "1_1") (pintype "passive"))
      (node (ref "J6") (pin "5") (pinfunction "5S_5") (pintype "passive"))
      (node (ref "R2") (pin "1") (pinfunction "1_1") (pintype "passive"))
    )
    (net (code "62") (name "/EXT-GPIO2-B") (class "Default")
      (node (ref "J1") (pin "1") (pinfunction "1_1") (pintype "passive"))
      (node (ref "J5") (pin "5") (pinfunction "5S_5") (pintype "passive"))
      (node (ref "R1") (pin "1") (pinfunction "1_1") (pintype "passive"))
    )
    (net (code "63") (name "/EXT-GPIO3-A") (class "Default")
      (node (ref "J2") (pin "3") (pinfunction "3_3") (pintype "passive"))
      (node (ref "J6") (pin "6") (pinfunction "6S_6") (pintype "passive"))
      (node (ref "R4") (pin "1") (pinfunction "1_1") (pintype "passive"))
    )
    (net (code "64") (name "/EXT-GPIO3-B") (class "Default")
      (node (ref "J1") (pin "3") (pinfunction "3_3") (pintype "passive"))
      (node (ref "J5") (pin "6") (pinfunction "6S_6") (pintype "passive"))
      (node (ref "R3") (pin "1") (pinfunction "1_1") (pintype "passive"))
    )
    (net (code "65") (name "/GPIO15_CAM1_PWDN") (class "Default")
      (node (ref "J10") (pin "90") (pinfunction "90_90") (pintype "passive"))
      (node (ref "U1") (pin "4") (pinfunction "A3_4") (pintype "bidirectional"))
    )
    (net (code "66") (name "/GPIO15_CAM1_PWDN_3V3") (class "Default")
      (node (ref "J1") (pin "2") (pinfunction "2_2") (pintype "passive"))
      (node (ref "R1") (pin "2") (pinfunction "2_2") (pintype "passive"))
      (node (ref "U1") (pin "8") (pinfunction "B3_8") (pintype "bidirectional"))
    )
    (net (code "67") (name "/GPIO16_CAM1_RST") (class "Default")
      (node (ref "J10") (pin "92") (pinfunction "92_92") (pintype "passive"))
      (node (ref "R21") (pin "1") (pinfunction "1_1") (pintype "passive"))
      (node (ref "TP6") (pin "1") (pinfunction "1_1") (pintype "passive"))
    )
    (net (code "68") (name "/GPIO25_VDD_SYS_EN") (class "Default")
      (node (ref "J10") (pin "119") (pinfunction "119_119") (pintype "passive"))
      (node (ref "TP1") (pin "1") (pinfunction "1_1") (pintype "passive"))
    )
    (net (code "69") (name "/I2C_CAM_CLK") (class "Default")
      (node (ref "J4") (pin "2") (pinfunction "2_2") (pintype "passive"))
      (node (ref "R15") (pin "2") (pinfunction "2_2") (pintype "passive"))
      (node (ref "R17") (pin "1") (pinfunction "1_1") (pintype "passive"))
      (node (ref "U3") (pin "6") (pinfunction "SCL2_6") (pintype "output"))
    )
    (net (code "70") (name "/I2C_CAM_CLK_1V8") (class "Default")
      (node (ref "J10") (pin "75") (pinfunction "75_75") (pintype "passive"))
      (node (ref "R13") (pin "2") (pinfunction "2_2") (pintype "passive"))
      (node (ref "U3") (pin "3") (pinfunction "SCL1_3") (pintype "input"))
    )
    (net (code "71") (name "/I2C_CAM_DAT") (class "Default")
      (node (ref "J4") (pin "4") (pinfunction "4_4") (pintype "passive"))
      (node (ref "R16") (pin "2") (pinfunction "2_2") (pintype "passive"))
      (node (ref "R18") (pin "1") (pinfunction "1_1") (pintype "passive"))
      (node (ref "U3") (pin "5") (pinfunction "SDA2_5") (pintype "bidirectional"))
    )
    (net (code "72") (name "/I2C_CAM_DAT_1V8") (class "Default")
      (node (ref "J10") (pin "77") (pinfunction "77_77") (pintype "passive"))
      (node (ref "R14") (pin "2") (pinfunction "2_2") (pintype "passive"))
      (node (ref "U3") (pin "4") (pinfunction "SDA1_4") (pintype "bidirectional"))
    )
    (net (code "73") (name "/I2C_GP0_CLK") (class "Default")
      (node (ref "J3") (pin "2") (pinfunction "2_2") (pintype "passive"))
      (node (ref "R10") (pin "1") (pinfunction "1_1") (pintype "passive"))
      (node (ref "R7") (pin "2") (pinfunction "2_2") (pintype "passive"))
      (node (ref "U2") (pin "6") (pinfunction "SCL2_6") (pintype "output"))
    )
    (net (code "74") (name "/I2C_GP0_CLK_1V8") (class "Default")
      (node (ref "J10") (pin "105") (pinfunction "105_105") (pintype "passive"))
      (node (ref "R5") (pin "2") (pinfunction "2_2") (pintype "passive"))
      (node (ref "U2") (pin "3") (pinfunction "SCL1_3") (pintype "input"))
    )
    (net (code "75") (name "/I2C_GP0_DAT") (class "Default")
      (node (ref "J3") (pin "4") (pinfunction "4_4") (pintype "passive"))
      (node (ref "R11") (pin "1") (pinfunction "1_1") (pintype "passive"))
      (node (ref "R8") (pin "2") (pinfunction "2_2") (pintype "passive"))
      (node (ref "U2") (pin "5") (pinfunction "SDA2_5") (pintype "bidirectional"))
    )
    (net (code "76") (name "/I2C_GP0_DAT_1V8") (class "Default")
      (node (ref "J10") (pin "107") (pinfunction "107_107") (pintype "passive"))
      (node (ref "R6") (pin "2") (pinfunction "2_2") (pintype "passive"))
      (node (ref "U2") (pin "4") (pinfunction "SDA1_4") (pintype "bidirectional"))
    )
    (net (code "77") (name "/I2C_PM_CLK_1V8") (class "Default")
      (node (ref "J10") (pin "87") (pinfunction "87_87") (pintype "passive"))
      (node (ref "TP5") (pin "1") (pinfunction "1_1") (pintype "passive"))
    )
    (net (code "78") (name "/I2C_PM_DAT_1V8") (class "Default")
      (node (ref "J10") (pin "89") (pinfunction "89_89") (pintype "passive"))
      (node (ref "TP3") (pin "1") (pinfunction "1_1") (pintype "passive"))
    )
    (net (code "79") (name "/XA_GND1") (class "Default")
      (node (ref "J10") (pin "63") (pinfunction "63_63") (pintype "passive+no_connect"))
    )
    (net (code "80") (name "/XA_GND2") (class "Default")
      (node (ref "J10") (pin "64") (pinfunction "64_64") (pintype "passive+no_connect"))
    )
    (net (code "81") (name "C-GND") (class "Default")
      (node (ref "C13") (pin "2") (pinfunction "2_2") (pintype "passive"))
      (node (ref "J9") (pin "6") (pinfunction "SH_6") (pintype "passive"))
      (node (ref "J9") (pin "7") (pinfunction "SH_7") (pintype "passive"))
      (node (ref "J9") (pin "8") (pinfunction "SH_8") (pintype "passive"))
      (node (ref "J9") (pin "9") (pinfunction "SH_9") (pintype "passive"))
      (node (ref "R27") (pin "1") (pinfunction "1_1") (pintype "passive"))
      (node (ref "X2") (pin "1") (pinfunction "1_1") (pintype "passive"))
    )
    (net (code "82") (name "GND") (class "Default")
      (node (ref "C1") (pin "2") (pinfunction "2_2") (pintype "passive"))
      (node (ref "C10") (pin "2") (pinfunction "2_2") (pintype "passive"))
      (node (ref "C11") (pin "2") (pinfunction "2_2") (pintype "passive"))
      (node (ref "C12") (pin "2") (pinfunction "2_2") (pintype "passive"))
      (node (ref "C13") (pin "1") (pinfunction "1_1") (pintype "passive"))
      (node (ref "C2") (pin "2") (pinfunction "2_2") (pintype "passive"))
      (node (ref "C3") (pin "2") (pinfunction "2_2") (pintype "passive"))
      (node (ref "C4") (pin "2") (pinfunction "2_2") (pintype "passive"))
      (node (ref "C5") (pin "2") (pinfunction "2_2") (pintype "passive"))
      (node (ref "C6") (pin "2") (pinfunction "2_2") (pintype "passive"))
      (node (ref "C7") (pin "2") (pinfunction "2_2") (pintype "passive"))
      (node (ref "C8") (pin "2") (pinfunction "2_2") (pintype "passive"))
      (node (ref "C9") (pin "2") (pinfunction "2_2") (pintype "passive"))
      (node (ref "D1") (pin "K") (pinfunction "2_K") (pintype "passive"))
      (node (ref "D2") (pin "K") (pinfunction "2_K") (pintype "passive"))
      (node (ref "D3") (pin "A") (pinfunction "A_A") (pintype "passive"))
      (node (ref "D4") (pin "A") (pinfunction "A_A") (pintype "passive"))
      (node (ref "J10") (pin "100") (pinfunction "100_100") (pintype "passive"))
      (node (ref "J10") (pin "11") (pinfunction "11_11") (pintype "passive"))
      (node (ref "J10") (pin "115") (pinfunction "115_115") (pintype "passive"))
      (node (ref "J10") (pin "116") (pinfunction "116_116") (pintype "passive"))
      (node (ref "J10") (pin "12") (pinfunction "12_12") (pintype "passive"))
      (node (ref "J10") (pin "121") (pinfunction "121_121") (pintype "passive"))
      (node (ref "J10") (pin "122") (pinfunction "122_122") (pintype "passive"))
      (node (ref "J10") (pin "123") (pinfunction "123_123") (pintype "passive"))
      (node (ref "J10") (pin "124") (pinfunction "124_124") (pintype "passive"))
      (node (ref "J10") (pin "125") (pinfunction "125_125") (pintype "passive"))
      (node (ref "J10") (pin "126") (pinfunction "126_126") (pintype "passive"))
      (node (ref "J10") (pin "127") (pinfunction "127_127") (pintype "passive"))
      (node (ref "J10") (pin "128") (pinfunction "128_128") (pintype "passive"))
      (node (ref "J10") (pin "17") (pinfunction "17_17") (pintype "passive"))
      (node (ref "J10") (pin "18") (pinfunction "18_18") (pintype "passive"))
      (node (ref "J10") (pin "23") (pinfunction "23_23") (pintype "passive"))
      (node (ref "J10") (pin "24") (pinfunction "24_24") (pintype "passive"))
      (node (ref "J10") (pin "29") (pinfunction "29_29") (pintype "passive"))
      (node (ref "J10") (pin "30") (pinfunction "30_30") (pintype "passive"))
      (node (ref "J10") (pin "35") (pinfunction "35_35") (pintype "passive"))
      (node (ref "J10") (pin "36") (pinfunction "36_36") (pintype "passive"))
      (node (ref "J10") (pin "41") (pinfunction "41_41") (pintype "passive"))
      (node (ref "J10") (pin "42") (pinfunction "42_42") (pintype "passive"))
      (node (ref "J10") (pin "47") (pinfunction "47_47") (pintype "passive"))
      (node (ref "J10") (pin "48") (pinfunction "48_48") (pintype "passive"))
      (node (ref "J10") (pin "5") (pinfunction "5_5") (pintype "passive"))
      (node (ref "J10") (pin "53") (pinfunction "53_53") (pintype "passive"))
      (node (ref "J10") (pin "54") (pinfunction "54_54") (pintype "passive"))
      (node (ref "J10") (pin "6") (pinfunction "6_6") (pintype "passive"))
      (node (ref "J10") (pin "69") (pinfunction "69_69") (pintype "passive"))
      (node (ref "J10") (pin "70") (pinfunction "70_70") (pintype "passive"))
      (node (ref "J10") (pin "79") (pinfunction "79_79") (pintype "passive"))
      (node (ref "J10") (pin "80") (pinfunction "80_80") (pintype "passive"))
      (node (ref "J10") (pin "99") (pinfunction "99_99") (pintype "passive"))
      (node (ref "J5") (pin "10") (pinfunction "10_10") (pintype "passive"))
      (node (ref "J5") (pin "13") (pinfunction "13_13") (pintype "passive"))
      (node (ref "J5") (pin "16") (pinfunction "16_16") (pintype "passive"))
      (node (ref "J5") (pin "19") (pinfunction "19_19") (pintype "passive"))
      (node (ref "J5") (pin "22") (pinfunction "22_22") (pintype "passive"))
      (node (ref "J6") (pin "10") (pinfunction "10_10") (pintype "passive"))
      (node (ref "J6") (pin "13") (pinfunction "13_13") (pintype "passive"))
      (node (ref "J6") (pin "16") (pinfunction "16_16") (pintype "passive"))
      (node (ref "J6") (pin "19") (pinfunction "19_19") (pintype "passive"))
      (node (ref "J6") (pin "22") (pinfunction "22_22") (pintype "passive"))
      (node (ref "J7") (pin "2") (pinfunction "2_2") (pintype "passive"))
      (node (ref "J9") (pin "5") (pinfunction "GND_5") (pintype "passive"))
      (node (ref "R23") (pin "1") (pinfunction "1_1") (pintype "passive"))
      (node (ref "R26") (pin "1") (pinfunction "1_1") (pintype "passive"))
      (node (ref "R27") (pin "2") (pinfunction "2_2") (pintype "passive"))
      (node (ref "U1") (pin "6") (pinfunction "GND_6") (pintype "power_in"))
      (node (ref "U2") (pin "1") (pinfunction "GND_1") (pintype "power_in"))
      (node (ref "U3") (pin "1") (pinfunction "GND_1") (pintype "power_in"))
      (node (ref "U4") (pin "5") (pinfunction "GND_5") (pintype "power_in"))
      (node (ref "U4") (pin "7") (pinfunction "(EP)GND_7") (pintype "power_in"))
      (node (ref "U5") (pin "5") (pinfunction "GND_5") (pintype "power_in"))
      (node (ref "U5") (pin "7") (pinfunction "(EP)GND_7") (pintype "power_in"))
    )
    (net (code "83") (name "Net-(D1-1)") (class "Default")
      (node (ref "D1") (pin "A") (pinfunction "1_A") (pintype "passive"))
      (node (ref "R9") (pin "2") (pinfunction "2_2") (pintype "passive"))
    )
    (net (code "84") (name "Net-(D2-1)") (class "Default")
      (node (ref "D2") (pin "A") (pinfunction "1_A") (pintype "passive"))
      (node (ref "R20") (pin "2") (pinfunction "2_2") (pintype "passive"))
    )
    (net (code "85") (name "Net-(U2-EN)") (class "Default")
      (node (ref "C4") (pin "1") (pinfunction "1_1") (pintype "passive"))
      (node (ref "R12") (pin "1") (pinfunction "1_1") (pintype "passive"))
      (node (ref "U2") (pin "7") (pinfunction "VREF2_7") (pintype "power_in"))
      (node (ref "U2") (pin "8") (pinfunction "EN_8") (pintype "input"))
    )
    (net (code "86") (name "Net-(U3-EN)") (class "Default")
      (node (ref "C6") (pin "1") (pinfunction "1_1") (pintype "passive"))
      (node (ref "R19") (pin "1") (pinfunction "1_1") (pintype "passive"))
      (node (ref "U3") (pin "7") (pinfunction "VREF2_7") (pintype "power_in"))
      (node (ref "U3") (pin "8") (pinfunction "EN_8") (pintype "input"))
    )
    (net (code "87") (name "Net-(U4-EN)") (class "Default")
      (node (ref "C7") (pin "1") (pinfunction "1_1") (pintype "passive"))
      (node (ref "R21") (pin "2") (pinfunction "2_2") (pintype "passive"))
      (node (ref "R22") (pin "1") (pinfunction "1_1") (pintype "passive"))
      (node (ref "U4") (pin "4") (pinfunction "EN_4") (pintype "input"))
    )
    (net (code "88") (name "Net-(U4-ILIM)") (class "Default")
      (node (ref "R23") (pin "2") (pinfunction "2_2") (pintype "passive"))
      (node (ref "U4") (pin "2") (pinfunction "ILIM_2") (pintype "input"))
    )
    (net (code "89") (name "Net-(U5-EN)") (class "Default")
      (node (ref "C10") (pin "1") (pinfunction "1_1") (pintype "passive"))
      (node (ref "R24") (pin "2") (pinfunction "2_2") (pintype "passive"))
      (node (ref "R25") (pin "1") (pinfunction "1_1") (pintype "passive"))
      (node (ref "U5") (pin "4") (pinfunction "EN_4") (pintype "input"))
    )
    (net (code "90") (name "Net-(U5-ILIM)") (class "Default")
      (node (ref "R26") (pin "2") (pinfunction "2_2") (pintype "passive"))
      (node (ref "U5") (pin "2") (pinfunction "ILIM_2") (pintype "input"))
    )
    (net (code "91") (name "VCC-EXT-IN") (class "Default")
      (node (ref "C11") (pin "1") (pinfunction "1_1") (pintype "passive"))
      (node (ref "C8") (pin "1") (pinfunction "1_1") (pintype "passive"))
      (node (ref "D3") (pin "K") (pinfunction "K_K") (pintype "passive"))
      (node (ref "D4") (pin "K") (pinfunction "K_K") (pintype "passive"))
      (node (ref "J7") (pin "1") (pinfunction "1_1") (pintype "passive"))
      (node (ref "J8") (pin "1") (pinfunction "1_1") (pintype "passive"))
      (node (ref "J9") (pin "1") (pinfunction "VCC_1") (pintype "passive"))
      (node (ref "R22") (pin "2") (pinfunction "2_2") (pintype "passive"))
      (node (ref "R25") (pin "2") (pinfunction "2_2") (pintype "passive"))
      (node (ref "U4") (pin "6") (pinfunction "IN_6") (pintype "power_in"))
      (node (ref "U5") (pin "6") (pinfunction "IN_6") (pintype "power_in"))
    )
    (net (code "92") (name "VCC-EXT-IN-A") (class "Default")
      (node (ref "C12") (pin "1") (pinfunction "1_1") (pintype "passive"))
      (node (ref "J6") (pin "1") (pinfunction "1_1") (pintype "passive"))
      (node (ref "J6") (pin "4") (pinfunction "4_4") (pintype "passive"))
      (node (ref "J6") (pin "7") (pinfunction "7_7") (pintype "passive"))
      (node (ref "R20") (pin "1") (pinfunction "1_1") (pintype "passive"))
      (node (ref "U5") (pin "1") (pinfunction "OUT_1") (pintype "power_in"))
    )
    (net (code "93") (name "VCC-EXT-IN-B") (class "Default")
      (node (ref "C9") (pin "1") (pinfunction "1_1") (pintype "passive"))
      (node (ref "J5") (pin "1") (pinfunction "1_1") (pintype "passive"))
      (node (ref "J5") (pin "4") (pinfunction "4_4") (pintype "passive"))
      (node (ref "J5") (pin "7") (pinfunction "7_7") (pintype "passive"))
      (node (ref "R9") (pin "1") (pinfunction "1_1") (pintype "passive"))
      (node (ref "U4") (pin "1") (pinfunction "OUT_1") (pintype "power_in"))
    )
    (net (code "94") (name "VCC1V8") (class "Default")
      (node (ref "C1") (pin "1") (pinfunction "1_1") (pintype "passive"))
      (node (ref "C3") (pin "1") (pinfunction "1_1") (pintype "passive"))
      (node (ref "C5") (pin "1") (pinfunction "1_1") (pintype "passive"))
      (node (ref "J10") (pin "102") (pinfunction "102_102") (pintype "passive"))
      (node (ref "R13") (pin "1") (pinfunction "1_1") (pintype "passive"))
      (node (ref "R14") (pin "1") (pinfunction "1_1") (pintype "passive"))
      (node (ref "R5") (pin "1") (pinfunction "1_1") (pintype "passive"))
      (node (ref "R6") (pin "1") (pinfunction "1_1") (pintype "passive"))
      (node (ref "U1") (pin "1") (pinfunction "VCCA_1") (pintype "power_in"))
      (node (ref "U1") (pin "12") (pinfunction "OE_12") (pintype "input"))
      (node (ref "U2") (pin "2") (pinfunction "VREF1_2") (pintype "power_in"))
      (node (ref "U3") (pin "2") (pinfunction "VREF1_2") (pintype "power_in"))
    )
    (net (code "95") (name "VCC2V8") (class "Default")
      (node (ref "J10") (pin "81") (pinfunction "81_81") (pintype "passive"))
      (node (ref "J10") (pin "82") (pinfunction "82_82") (pintype "passive"))
      (node (ref "J10") (pin "83") (pinfunction "83_83") (pintype "passive"))
      (node (ref "TP7") (pin "1") (pinfunction "1_1") (pintype "passive"))
    )
    (net (code "96") (name "VCC3V3") (class "Default")
      (node (ref "C2") (pin "1") (pinfunction "1_1") (pintype "passive"))
      (node (ref "J10") (pin "108") (pinfunction "108_108") (pintype "passive"))
      (node (ref "J10") (pin "110") (pinfunction "110_110") (pintype "passive"))
      (node (ref "R10") (pin "2") (pinfunction "2_2") (pintype "passive"))
      (node (ref "R11") (pin "2") (pinfunction "2_2") (pintype "passive"))
      (node (ref "R12") (pin "2") (pinfunction "2_2") (pintype "passive"))
      (node (ref "R17") (pin "2") (pinfunction "2_2") (pintype "passive"))
      (node (ref "R18") (pin "2") (pinfunction "2_2") (pintype "passive"))
      (node (ref "R19") (pin "2") (pinfunction "2_2") (pintype "passive"))
      (node (ref "U1") (pin "11") (pinfunction "VCCB_11") (pintype "power_in"))
    )
    (net (code "97") (name "XA-VCC3V3_TX2-VCC5V") (class "Default")
      (node (ref "J10") (pin "118") (pinfunction "118_118") (pintype "passive"))
      (node (ref "J10") (pin "120") (pinfunction "120_120") (pintype "passive"))
      (node (ref "J8") (pin "2") (pinfunction "2_2") (pintype "passive"))
    )
    (net (code "98") (name "unconnected-(J5-Pad23)") (class "Default")
      (node (ref "J5") (pin "23") (pinfunction "23_23") (pintype "passive+no_connect"))
    )
    (net (code "99") (name "unconnected-(J5-Pad24)") (class "Default")
      (node (ref "J5") (pin "24") (pinfunction "24_24") (pintype "passive+no_connect"))
    )
    (net (code "100") (name "unconnected-(J6-Pad23)") (class "Default")
      (node (ref "J6") (pin "23") (pinfunction "23_23") (pintype "passive+no_connect"))
    )
    (net (code "101") (name "unconnected-(J6-Pad24)") (class "Default")
      (node (ref "J6") (pin "24") (pinfunction "24_24") (pintype "passive+no_connect"))
    )
    (net (code "102") (name "unconnected-(J9-D+-Pad3)") (class "Default")
      (node (ref "J9") (pin "3") (pinfunction "D+_3") (pintype "passive+no_connect"))
    )
    (net (code "103") (name "unconnected-(J9-D--Pad2)") (class "Default")
      (node (ref "J9") (pin "2") (pinfunction "D-_2") (pintype "passive+no_connect"))
    )
    (net (code "104") (name "unconnected-(J9-ID-Pad4)") (class "Default")
      (node (ref "J9") (pin "4") (pinfunction "ID_4") (pintype "passive+no_connect"))
    )
    (net (code "105") (name "unconnected-(J10-Pad55)") (class "Default")
      (node (ref "J10") (pin "55") (pinfunction "55_55") (pintype "passive+no_connect"))
    )
    (net (code "106") (name "unconnected-(J10-Pad56)") (class "Default")
      (node (ref "J10") (pin "56") (pinfunction "56_56") (pintype "passive+no_connect"))
    )
    (net (code "107") (name "unconnected-(J10-Pad57)") (class "Default")
      (node (ref "J10") (pin "57") (pinfunction "57_57") (pintype "passive+no_connect"))
    )
    (net (code "108") (name "unconnected-(J10-Pad58)") (class "Default")
      (node (ref "J10") (pin "58") (pinfunction "58_58") (pintype "passive+no_connect"))
    )
    (net (code "109") (name "unconnected-(J10-Pad76)") (class "Default")
      (node (ref "J10") (pin "76") (pinfunction "76_76") (pintype "passive+no_connect"))
    )
    (net (code "110") (name "unconnected-(J10-Pad78)") (class "Default")
      (node (ref "J10") (pin "78") (pinfunction "78_78") (pintype "passive+no_connect"))
    )
    (net (code "111") (name "unconnected-(J10-Pad84)") (class "Default")
      (node (ref "J10") (pin "84") (pinfunction "84_84") (pintype "passive+no_connect"))
    )
    (net (code "112") (name "unconnected-(J10-Pad85)") (class "Default")
      (node (ref "J10") (pin "85") (pinfunction "85_85") (pintype "passive+no_connect"))
    )
    (net (code "113") (name "unconnected-(J10-Pad86)") (class "Default")
      (node (ref "J10") (pin "86") (pinfunction "86_86") (pintype "passive+no_connect"))
    )
    (net (code "114") (name "unconnected-(J10-Pad96)") (class "Default")
      (node (ref "J10") (pin "96") (pinfunction "96_96") (pintype "passive+no_connect"))
    )
    (net (code "115") (name "unconnected-(J10-Pad97)") (class "Default")
      (node (ref "J10") (pin "97") (pinfunction "97_97") (pintype "passive+no_connect"))
    )
    (net (code "116") (name "unconnected-(J10-Pad98)") (class "Default")
      (node (ref "J10") (pin "98") (pinfunction "98_98") (pintype "passive+no_connect"))
    )
    (net (code "117") (name "unconnected-(J10-Pad101)") (class "Default")
      (node (ref "J10") (pin "101") (pinfunction "101_101") (pintype "passive+no_connect"))
    )
    (net (code "118") (name "unconnected-(J10-Pad103)") (class "Default")
      (node (ref "J10") (pin "103") (pinfunction "103_103") (pintype "passive+no_connect"))
    )
    (net (code "119") (name "unconnected-(J10-Pad104)") (class "Default")
      (node (ref "J10") (pin "104") (pinfunction "104_104") (pintype "passive+no_connect"))
    )
    (net (code "120") (name "unconnected-(J10-Pad106)") (class "Default")
      (node (ref "J10") (pin "106") (pinfunction "106_106") (pintype "passive+no_connect"))
    )
    (net (code "121") (name "unconnected-(J10-Pad109)") (class "Default")
      (node (ref "J10") (pin "109") (pinfunction "109_109") (pintype "passive+no_connect"))
    )
    (net (code "122") (name "unconnected-(J10-Pad111)") (class "Default")
      (node (ref "J10") (pin "111") (pinfunction "111_111") (pintype "passive+no_connect"))
    )
    (net (code "123") (name "unconnected-(J10-Pad112)") (class "Default")
      (node (ref "J10") (pin "112") (pinfunction "112_112") (pintype "passive+no_connect"))
    )
    (net (code "124") (name "unconnected-(J10-Pad113)") (class "Default")
      (node (ref "J10") (pin "113") (pinfunction "113_113") (pintype "passive+no_connect"))
    )
    (net (code "125") (name "unconnected-(J10-Pad114)") (class "Default")
      (node (ref "J10") (pin "114") (pinfunction "114_114") (pintype "passive+no_connect"))
    )
    (net (code "126") (name "unconnected-(J10-Pad117)") (class "Default")
      (node (ref "J10") (pin "117") (pinfunction "117_117") (pintype "passive+no_connect"))
    )
    (net (code "127") (name "unconnected-(U4-~{FAULT}-Pad3)") (class "Default")
      (node (ref "U4") (pin "3") (pinfunction "~{FAULT}_3") (pintype "output+no_connect"))
    )
    (net (code "128") (name "unconnected-(U5-~{FAULT}-Pad3)") (class "Default")
      (node (ref "U5") (pin "3") (pinfunction "~{FAULT}_3") (pintype "output+no_connect"))
    )
    (net (code "129") (name "unconnected-(X1-Pad1)") (class "Default")
      (node (ref "X1") (pin "1") (pinfunction "1_1") (pintype "passive+no_connect"))
    )
  )
)
